# FPGA_Connector_1.net
KiCad netlist of a schematic drawn in Altium Designer
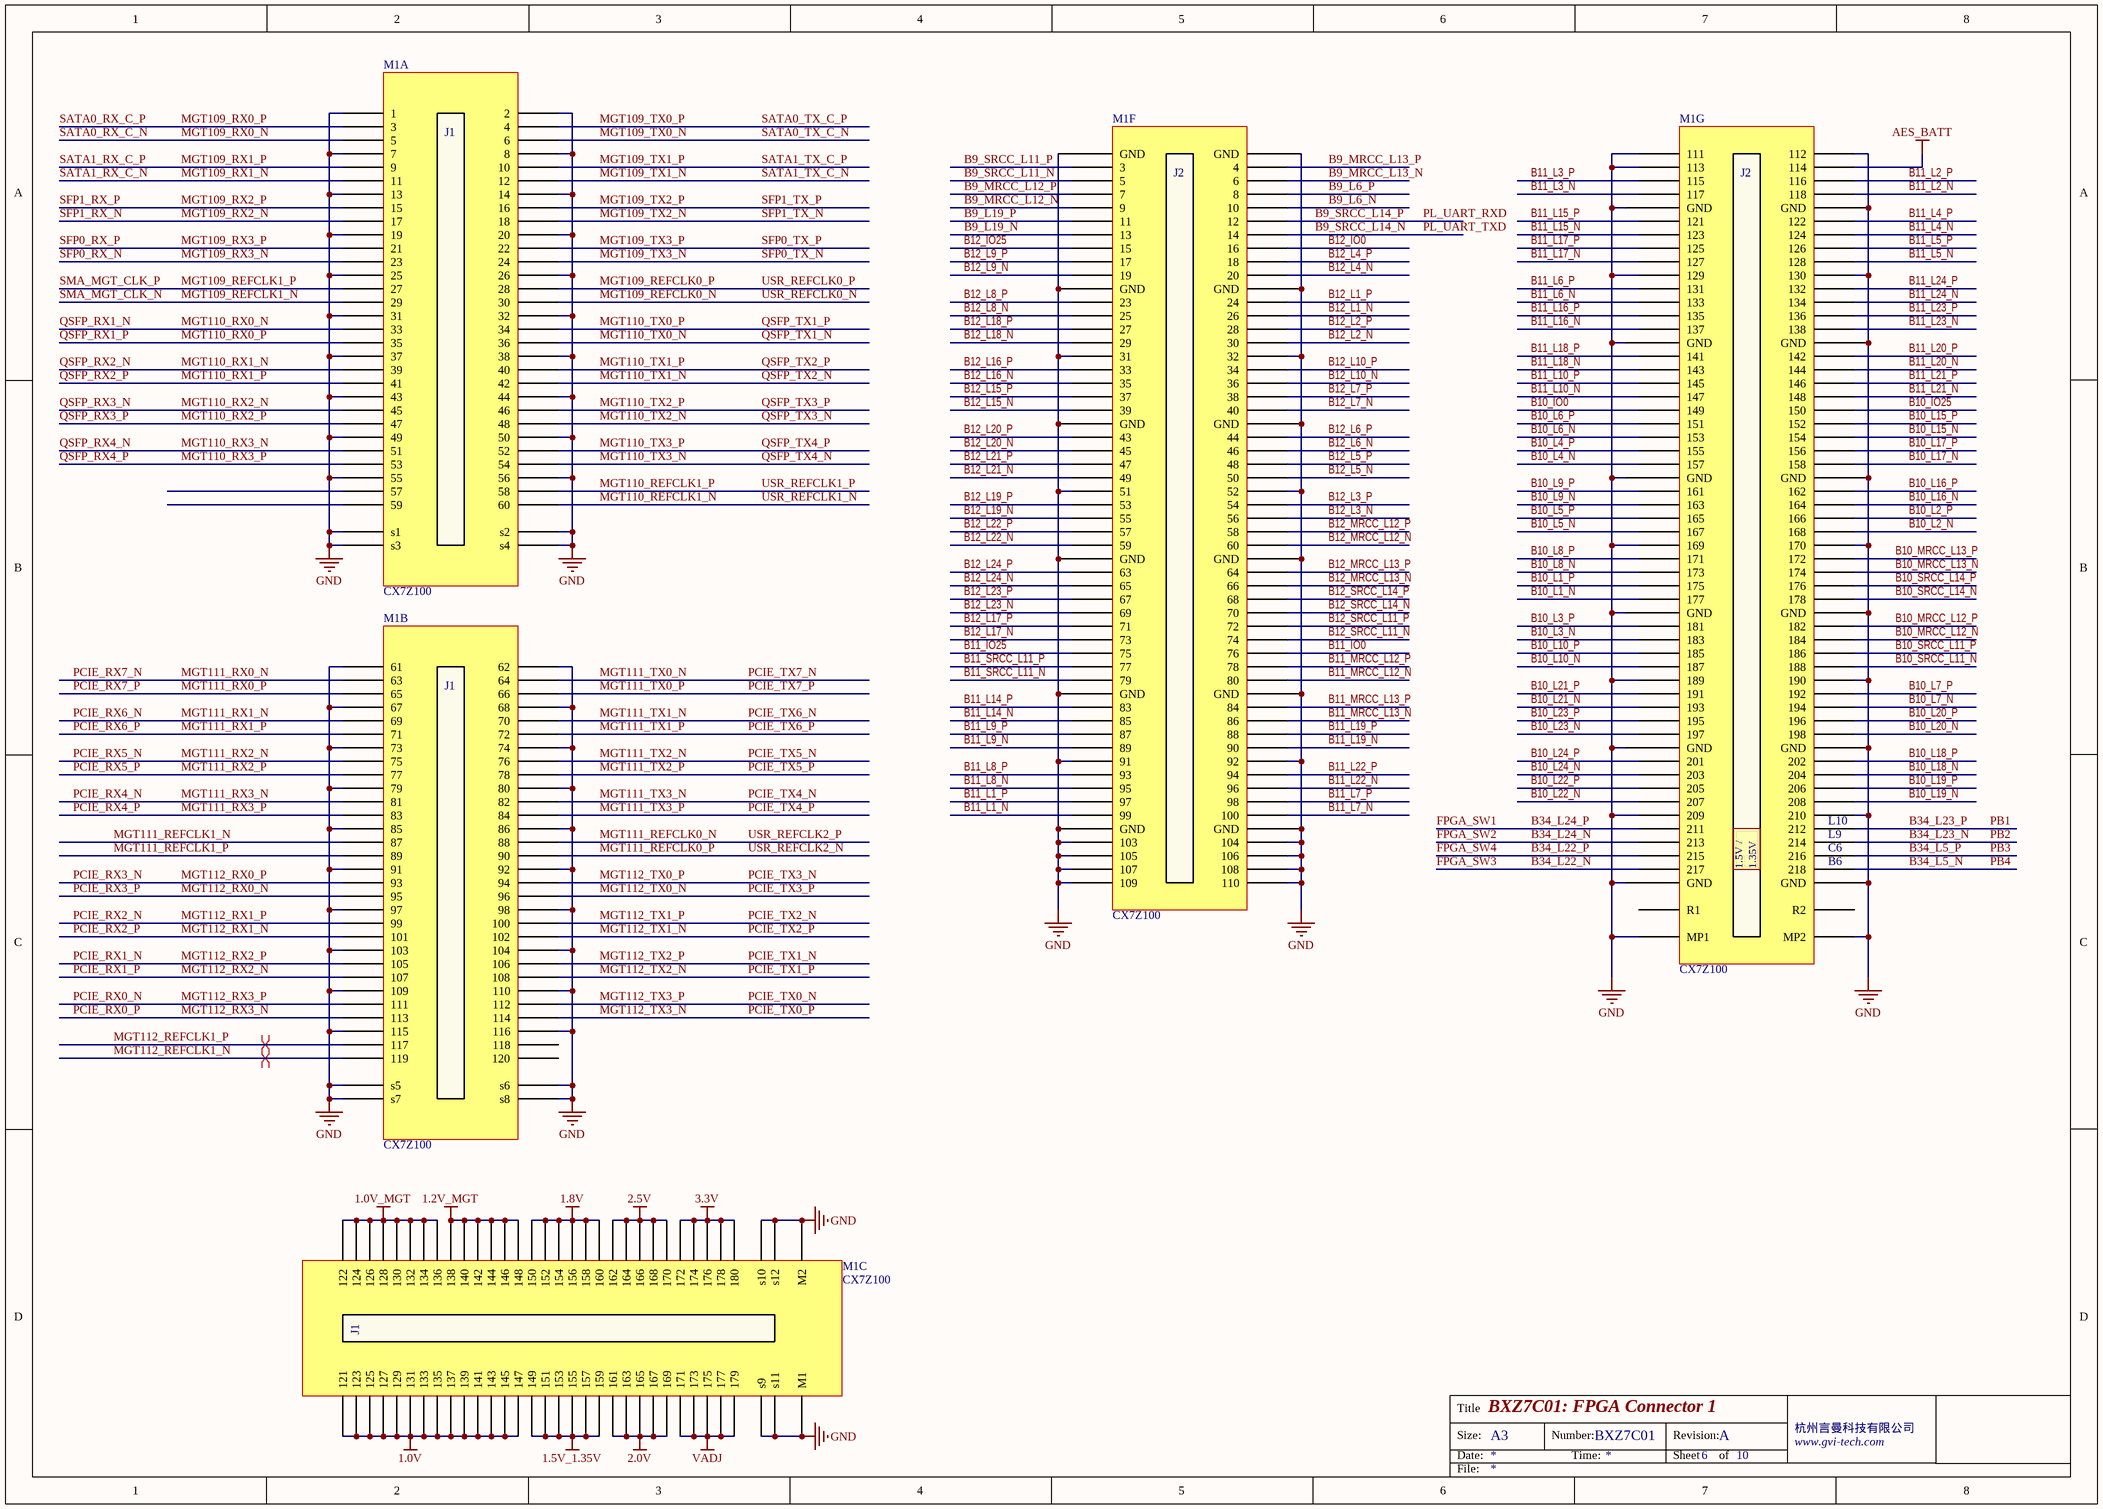
[diagram p0: FPGA_Connector_1.SchDoc]

(export (version "E")
  (design (tool "Eeschema 10.0.6"))
  (components
    (comp (ref "M1")
      (value "CX7Z100")
      (footprint "GVI_Z7_MiniModule_Socket")
      (libsource (lib "GVI_Z7_Carrier") (part "CX7Z100"))
    )
  )
  (nets
    (net (code "1") (name "/B9_L6_N") (class "Default")
      (node (ref "M1") (pin "B10") (pinfunction "10_B10") (pintype "passive"))
    )
    (net (code "2") (name "/B9_L6_P") (class "Default")
      (node (ref "M1") (pin "B8") (pinfunction "8_B8") (pintype "passive"))
    )
    (net (code "3") (name "/B9_L19_N") (class "Default")
      (node (ref "M1") (pin "B13") (pinfunction "13_B13") (pintype "passive"))
    )
    (net (code "4") (name "/B9_L19_P") (class "Default")
      (node (ref "M1") (pin "B11") (pinfunction "11_B11") (pintype "passive"))
    )
    (net (code "5") (name "/B9_MRCC_L12_N") (class "Default")
      (node (ref "M1") (pin "B9") (pinfunction "9_B9") (pintype "passive"))
    )
    (net (code "6") (name "/B9_MRCC_L12_P") (class "Default")
      (node (ref "M1") (pin "B7") (pinfunction "7_B7") (pintype "passive"))
    )
    (net (code "7") (name "/B9_MRCC_L13_N") (class "Default")
      (node (ref "M1") (pin "B6") (pinfunction "6_B6") (pintype "passive"))
    )
    (net (code "8") (name "/B9_MRCC_L13_P") (class "Default")
      (node (ref "M1") (pin "B4") (pinfunction "4_B4") (pintype "passive"))
    )
    (net (code "9") (name "/B9_SRCC_L11_N") (class "Default")
      (node (ref "M1") (pin "B5") (pinfunction "5_B5") (pintype "passive"))
    )
    (net (code "10") (name "/B9_SRCC_L11_P") (class "Default")
      (node (ref "M1") (pin "B3") (pinfunction "3_B3") (pintype "passive"))
    )
    (net (code "11") (name "/B9_SRCC_L14_N") (class "Default")
      (node (ref "M1") (pin "B14") (pinfunction "14_B14") (pintype "passive"))
    )
    (net (code "12") (name "/B9_SRCC_L14_P") (class "Default")
      (node (ref "M1") (pin "B12") (pinfunction "12_B12") (pintype "passive"))
    )
    (net (code "13") (name "/B10_IO0") (class "Default")
      (node (ref "M1") (pin "B149") (pinfunction "149_B149") (pintype "passive"))
    )
    (net (code "14") (name "/B10_IO25") (class "Default")
      (node (ref "M1") (pin "B150") (pinfunction "150_B150") (pintype "passive"))
    )
    (net (code "15") (name "/B10_L1_N") (class "Default")
      (node (ref "M1") (pin "B177") (pinfunction "177_B177") (pintype "passive"))
    )
    (net (code "16") (name "/B10_L1_P") (class "Default")
      (node (ref "M1") (pin "B175") (pinfunction "175_B175") (pintype "passive"))
    )
    (net (code "17") (name "/B10_L2_N") (class "Default")
      (node (ref "M1") (pin "B168") (pinfunction "168_B168") (pintype "passive"))
    )
    (net (code "18") (name "/B10_L2_P") (class "Default")
      (node (ref "M1") (pin "B166") (pinfunction "166_B166") (pintype "passive"))
    )
    (net (code "19") (name "/B10_L3_N") (class "Default")
      (node (ref "M1") (pin "B183") (pinfunction "183_B183") (pintype "passive"))
    )
    (net (code "20") (name "/B10_L3_P") (class "Default")
      (node (ref "M1") (pin "B181") (pinfunction "181_B181") (pintype "passive"))
    )
    (net (code "21") (name "/B10_L4_N") (class "Default")
      (node (ref "M1") (pin "B157") (pinfunction "157_B157") (pintype "passive"))
    )
    (net (code "22") (name "/B10_L4_P") (class "Default")
      (node (ref "M1") (pin "B155") (pinfunction "155_B155") (pintype "passive"))
    )
    (net (code "23") (name "/B10_L5_N") (class "Default")
      (node (ref "M1") (pin "B167") (pinfunction "167_B167") (pintype "passive"))
    )
    (net (code "24") (name "/B10_L5_P") (class "Default")
      (node (ref "M1") (pin "B165") (pinfunction "165_B165") (pintype "passive"))
    )
    (net (code "25") (name "/B10_L6_N") (class "Default")
      (node (ref "M1") (pin "B153") (pinfunction "153_B153") (pintype "passive"))
    )
    (net (code "26") (name "/B10_L6_P") (class "Default")
      (node (ref "M1") (pin "B151") (pinfunction "151_B151") (pintype "passive"))
    )
    (net (code "27") (name "/B10_L7_N") (class "Default")
      (node (ref "M1") (pin "B194") (pinfunction "194_B194") (pintype "passive"))
    )
    (net (code "28") (name "/B10_L7_P") (class "Default")
      (node (ref "M1") (pin "B192") (pinfunction "192_B192") (pintype "passive"))
    )
    (net (code "29") (name "/B10_L8_N") (class "Default")
      (node (ref "M1") (pin "B173") (pinfunction "173_B173") (pintype "passive"))
    )
    (net (code "30") (name "/B10_L8_P") (class "Default")
      (node (ref "M1") (pin "B171") (pinfunction "171_B171") (pintype "passive"))
    )
    (net (code "31") (name "/B10_L9_N") (class "Default")
      (node (ref "M1") (pin "B163") (pinfunction "163_B163") (pintype "passive"))
    )
    (net (code "32") (name "/B10_L9_P") (class "Default")
      (node (ref "M1") (pin "B161") (pinfunction "161_B161") (pintype "passive"))
    )
    (net (code "33") (name "/B10_L10_N") (class "Default")
      (node (ref "M1") (pin "B187") (pinfunction "187_B187") (pintype "passive"))
    )
    (net (code "34") (name "/B10_L10_P") (class "Default")
      (node (ref "M1") (pin "B185") (pinfunction "185_B185") (pintype "passive"))
    )
    (net (code "35") (name "/B10_L15_N") (class "Default")
      (node (ref "M1") (pin "B154") (pinfunction "154_B154") (pintype "passive"))
    )
    (net (code "36") (name "/B10_L15_P") (class "Default")
      (node (ref "M1") (pin "B152") (pinfunction "152_B152") (pintype "passive"))
    )
    (net (code "37") (name "/B10_L16_N") (class "Default")
      (node (ref "M1") (pin "B164") (pinfunction "164_B164") (pintype "passive"))
    )
    (net (code "38") (name "/B10_L16_P") (class "Default")
      (node (ref "M1") (pin "B162") (pinfunction "162_B162") (pintype "passive"))
    )
    (net (code "39") (name "/B10_L17_N") (class "Default")
      (node (ref "M1") (pin "B158") (pinfunction "158_B158") (pintype "passive"))
    )
    (net (code "40") (name "/B10_L17_P") (class "Default")
      (node (ref "M1") (pin "B156") (pinfunction "156_B156") (pintype "passive"))
    )
    (net (code "41") (name "/B10_L18_N") (class "Default")
      (node (ref "M1") (pin "B204") (pinfunction "204_B204") (pintype "passive"))
    )
    (net (code "42") (name "/B10_L18_P") (class "Default")
      (node (ref "M1") (pin "B202") (pinfunction "202_B202") (pintype "passive"))
    )
    (net (code "43") (name "/B10_L19_N") (class "Default")
      (node (ref "M1") (pin "B208") (pinfunction "208_B208") (pintype "passive"))
    )
    (net (code "44") (name "/B10_L19_P") (class "Default")
      (node (ref "M1") (pin "B206") (pinfunction "206_B206") (pintype "passive"))
    )
    (net (code "45") (name "/B10_L20_N") (class "Default")
      (node (ref "M1") (pin "B198") (pinfunction "198_B198") (pintype "passive"))
    )
    (net (code "46") (name "/B10_L20_P") (class "Default")
      (node (ref "M1") (pin "B196") (pinfunction "196_B196") (pintype "passive"))
    )
    (net (code "47") (name "/B10_L21_N") (class "Default")
      (node (ref "M1") (pin "B193") (pinfunction "193_B193") (pintype "passive"))
    )
    (net (code "48") (name "/B10_L21_P") (class "Default")
      (node (ref "M1") (pin "B191") (pinfunction "191_B191") (pintype "passive"))
    )
    (net (code "49") (name "/B10_L22_N") (class "Default")
      (node (ref "M1") (pin "B207") (pinfunction "207_B207") (pintype "passive"))
    )
    (net (code "50") (name "/B10_L22_P") (class "Default")
      (node (ref "M1") (pin "B205") (pinfunction "205_B205") (pintype "passive"))
    )
    (net (code "51") (name "/B10_L23_N") (class "Default")
      (node (ref "M1") (pin "B197") (pinfunction "197_B197") (pintype "passive"))
    )
    (net (code "52") (name "/B10_L23_P") (class "Default")
      (node (ref "M1") (pin "B195") (pinfunction "195_B195") (pintype "passive"))
    )
    (net (code "53") (name "/B10_L24_N") (class "Default")
      (node (ref "M1") (pin "B203") (pinfunction "203_B203") (pintype "passive"))
    )
    (net (code "54") (name "/B10_L24_P") (class "Default")
      (node (ref "M1") (pin "B201") (pinfunction "201_B201") (pintype "passive"))
    )
    (net (code "55") (name "/B10_MRCC_L12_N") (class "Default")
      (node (ref "M1") (pin "B184") (pinfunction "184_B184") (pintype "passive"))
    )
    (net (code "56") (name "/B10_MRCC_L12_P") (class "Default")
      (node (ref "M1") (pin "B182") (pinfunction "182_B182") (pintype "passive"))
    )
    (net (code "57") (name "/B10_MRCC_L13_N") (class "Default")
      (node (ref "M1") (pin "B174") (pinfunction "174_B174") (pintype "passive"))
    )
    (net (code "58") (name "/B10_MRCC_L13_P") (class "Default")
      (node (ref "M1") (pin "B172") (pinfunction "172_B172") (pintype "passive"))
    )
    (net (code "59") (name "/B10_SRCC_L11_N") (class "Default")
      (node (ref "M1") (pin "B188") (pinfunction "188_B188") (pintype "passive"))
    )
    (net (code "60") (name "/B10_SRCC_L11_P") (class "Default")
      (node (ref "M1") (pin "B186") (pinfunction "186_B186") (pintype "passive"))
    )
    (net (code "61") (name "/B10_SRCC_L14_N") (class "Default")
      (node (ref "M1") (pin "B178") (pinfunction "178_B178") (pintype "passive"))
    )
    (net (code "62") (name "/B10_SRCC_L14_P") (class "Default")
      (node (ref "M1") (pin "B176") (pinfunction "176_B176") (pintype "passive"))
    )
    (net (code "63") (name "/B11_IO0") (class "Default")
      (node (ref "M1") (pin "B76") (pinfunction "76_B76") (pintype "passive"))
    )
    (net (code "64") (name "/B11_IO25") (class "Default")
      (node (ref "M1") (pin "B75") (pinfunction "75_B75") (pintype "passive"))
    )
    (net (code "65") (name "/B11_L1_N") (class "Default")
      (node (ref "M1") (pin "B99") (pinfunction "99_B99") (pintype "passive"))
    )
    (net (code "66") (name "/B11_L1_P") (class "Default")
      (node (ref "M1") (pin "B97") (pinfunction "97_B97") (pintype "passive"))
    )
    (net (code "67") (name "/B11_L2_N") (class "Default")
      (node (ref "M1") (pin "B118") (pinfunction "118_B118") (pintype "passive"))
    )
    (net (code "68") (name "/B11_L2_P") (class "Default")
      (node (ref "M1") (pin "B116") (pinfunction "116_B116") (pintype "passive"))
    )
    (net (code "69") (name "/B11_L3_N") (class "Default")
      (node (ref "M1") (pin "B117") (pinfunction "117_B117") (pintype "passive"))
    )
    (net (code "70") (name "/B11_L3_P") (class "Default")
      (node (ref "M1") (pin "B115") (pinfunction "115_B115") (pintype "passive"))
    )
    (net (code "71") (name "/B11_L4_N") (class "Default")
      (node (ref "M1") (pin "B124") (pinfunction "124_B124") (pintype "passive"))
    )
    (net (code "72") (name "/B11_L4_P") (class "Default")
      (node (ref "M1") (pin "B122") (pinfunction "122_B122") (pintype "passive"))
    )
    (net (code "73") (name "/B11_L5_N") (class "Default")
      (node (ref "M1") (pin "B128") (pinfunction "128_B128") (pintype "passive"))
    )
    (net (code "74") (name "/B11_L5_P") (class "Default")
      (node (ref "M1") (pin "B126") (pinfunction "126_B126") (pintype "passive"))
    )
    (net (code "75") (name "/B11_L6_N") (class "Default")
      (node (ref "M1") (pin "B133") (pinfunction "133_B133") (pintype "passive"))
    )
    (net (code "76") (name "/B11_L6_P") (class "Default")
      (node (ref "M1") (pin "B131") (pinfunction "131_B131") (pintype "passive"))
    )
    (net (code "77") (name "/B11_L7_N") (class "Default")
      (node (ref "M1") (pin "B100") (pinfunction "100_B100") (pintype "passive"))
    )
    (net (code "78") (name "/B11_L7_P") (class "Default")
      (node (ref "M1") (pin "B98") (pinfunction "98_B98") (pintype "passive"))
    )
    (net (code "79") (name "/B11_L8_N") (class "Default")
      (node (ref "M1") (pin "B95") (pinfunction "95_B95") (pintype "passive"))
    )
    (net (code "80") (name "/B11_L8_P") (class "Default")
      (node (ref "M1") (pin "B93") (pinfunction "93_B93") (pintype "passive"))
    )
    (net (code "81") (name "/B11_L9_N") (class "Default")
      (node (ref "M1") (pin "B89") (pinfunction "89_B89") (pintype "passive"))
    )
    (net (code "82") (name "/B11_L9_P") (class "Default")
      (node (ref "M1") (pin "B87") (pinfunction "87_B87") (pintype "passive"))
    )
    (net (code "83") (name "/B11_L10_N") (class "Default")
      (node (ref "M1") (pin "B147") (pinfunction "147_B147") (pintype "passive"))
    )
    (net (code "84") (name "/B11_L10_P") (class "Default")
      (node (ref "M1") (pin "B145") (pinfunction "145_B145") (pintype "passive"))
    )
    (net (code "85") (name "/B11_L14_N") (class "Default")
      (node (ref "M1") (pin "B85") (pinfunction "85_B85") (pintype "passive"))
    )
    (net (code "86") (name "/B11_L14_P") (class "Default")
      (node (ref "M1") (pin "B83") (pinfunction "83_B83") (pintype "passive"))
    )
    (net (code "87") (name "/B11_L15_N") (class "Default")
      (node (ref "M1") (pin "B123") (pinfunction "123_B123") (pintype "passive"))
    )
    (net (code "88") (name "/B11_L15_P") (class "Default")
      (node (ref "M1") (pin "B121") (pinfunction "121_B121") (pintype "passive"))
    )
    (net (code "89") (name "/B11_L16_N") (class "Default")
      (node (ref "M1") (pin "B137") (pinfunction "137_B137") (pintype "passive"))
    )
    (net (code "90") (name "/B11_L16_P") (class "Default")
      (node (ref "M1") (pin "B135") (pinfunction "135_B135") (pintype "passive"))
    )
    (net (code "91") (name "/B11_L17_N") (class "Default")
      (node (ref "M1") (pin "B127") (pinfunction "127_B127") (pintype "passive"))
    )
    (net (code "92") (name "/B11_L17_P") (class "Default")
      (node (ref "M1") (pin "B125") (pinfunction "125_B125") (pintype "passive"))
    )
    (net (code "93") (name "/B11_L18_N") (class "Default")
      (node (ref "M1") (pin "B143") (pinfunction "143_B143") (pintype "passive"))
    )
    (net (code "94") (name "/B11_L18_P") (class "Default")
      (node (ref "M1") (pin "B141") (pinfunction "141_B141") (pintype "passive"))
    )
    (net (code "95") (name "/B11_L19_N") (class "Default")
      (node (ref "M1") (pin "B90") (pinfunction "90_B90") (pintype "passive"))
    )
    (net (code "96") (name "/B11_L19_P") (class "Default")
      (node (ref "M1") (pin "B88") (pinfunction "88_B88") (pintype "passive"))
    )
    (net (code "97") (name "/B11_L20_N") (class "Default")
      (node (ref "M1") (pin "B144") (pinfunction "144_B144") (pintype "passive"))
    )
    (net (code "98") (name "/B11_L20_P") (class "Default")
      (node (ref "M1") (pin "B142") (pinfunction "142_B142") (pintype "passive"))
    )
    (net (code "99") (name "/B11_L21_N") (class "Default")
      (node (ref "M1") (pin "B148") (pinfunction "148_B148") (pintype "passive"))
    )
    (net (code "100") (name "/B11_L21_P") (class "Default")
      (node (ref "M1") (pin "B146") (pinfunction "146_B146") (pintype "passive"))
    )
    (net (code "101") (name "/B11_L22_N") (class "Default")
      (node (ref "M1") (pin "B96") (pinfunction "96_B96") (pintype "passive"))
    )
    (net (code "102") (name "/B11_L22_P") (class "Default")
      (node (ref "M1") (pin "B94") (pinfunction "94_B94") (pintype "passive"))
    )
    (net (code "103") (name "/B11_L23_N") (class "Default")
      (node (ref "M1") (pin "B138") (pinfunction "138_B138") (pintype "passive"))
    )
    (net (code "104") (name "/B11_L23_P") (class "Default")
      (node (ref "M1") (pin "B136") (pinfunction "136_B136") (pintype "passive"))
    )
    (net (code "105") (name "/B11_L24_N") (class "Default")
      (node (ref "M1") (pin "B134") (pinfunction "134_B134") (pintype "passive"))
    )
    (net (code "106") (name "/B11_L24_P") (class "Default")
      (node (ref "M1") (pin "B132") (pinfunction "132_B132") (pintype "passive"))
    )
    (net (code "107") (name "/B11_MRCC_L12_N") (class "Default")
      (node (ref "M1") (pin "B80") (pinfunction "80_B80") (pintype "passive"))
    )
    (net (code "108") (name "/B11_MRCC_L12_P") (class "Default")
      (node (ref "M1") (pin "B78") (pinfunction "78_B78") (pintype "passive"))
    )
    (net (code "109") (name "/B11_MRCC_L13_N") (class "Default")
      (node (ref "M1") (pin "B86") (pinfunction "86_B86") (pintype "passive"))
    )
    (net (code "110") (name "/B11_MRCC_L13_P") (class "Default")
      (node (ref "M1") (pin "B84") (pinfunction "84_B84") (pintype "passive"))
    )
    (net (code "111") (name "/B11_SRCC_L11_N") (class "Default")
      (node (ref "M1") (pin "B79") (pinfunction "79_B79") (pintype "passive"))
    )
    (net (code "112") (name "/B11_SRCC_L11_P") (class "Default")
      (node (ref "M1") (pin "B77") (pinfunction "77_B77") (pintype "passive"))
    )
    (net (code "113") (name "/B12_IO0") (class "Default")
      (node (ref "M1") (pin "B16") (pinfunction "16_B16") (pintype "passive"))
    )
    (net (code "114") (name "/B12_IO25") (class "Default")
      (node (ref "M1") (pin "B15") (pinfunction "15_B15") (pintype "passive"))
    )
    (net (code "115") (name "/B12_L1_N") (class "Default")
      (node (ref "M1") (pin "B26") (pinfunction "26_B26") (pintype "passive"))
    )
    (net (code "116") (name "/B12_L1_P") (class "Default")
      (node (ref "M1") (pin "B24") (pinfunction "24_B24") (pintype "passive"))
    )
    (net (code "117") (name "/B12_L2_N") (class "Default")
      (node (ref "M1") (pin "B30") (pinfunction "30_B30") (pintype "passive"))
    )
    (net (code "118") (name "/B12_L2_P") (class "Default")
      (node (ref "M1") (pin "B28") (pinfunction "28_B28") (pintype "passive"))
    )
    (net (code "119") (name "/B12_L3_N") (class "Default")
      (node (ref "M1") (pin "B56") (pinfunction "56_B56") (pintype "passive"))
    )
    (net (code "120") (name "/B12_L3_P") (class "Default")
      (node (ref "M1") (pin "B54") (pinfunction "54_B54") (pintype "passive"))
    )
    (net (code "121") (name "/B12_L4_N") (class "Default")
      (node (ref "M1") (pin "B20") (pinfunction "20_B20") (pintype "passive"))
    )
    (net (code "122") (name "/B12_L4_P") (class "Default")
      (node (ref "M1") (pin "B18") (pinfunction "18_B18") (pintype "passive"))
    )
    (net (code "123") (name "/B12_L5_N") (class "Default")
      (node (ref "M1") (pin "B50") (pinfunction "50_B50") (pintype "passive"))
    )
    (net (code "124") (name "/B12_L5_P") (class "Default")
      (node (ref "M1") (pin "B48") (pinfunction "48_B48") (pintype "passive"))
    )
    (net (code "125") (name "/B12_L6_N") (class "Default")
      (node (ref "M1") (pin "B46") (pinfunction "46_B46") (pintype "passive"))
    )
    (net (code "126") (name "/B12_L6_P") (class "Default")
      (node (ref "M1") (pin "B44") (pinfunction "44_B44") (pintype "passive"))
    )
    (net (code "127") (name "/B12_L7_N") (class "Default")
      (node (ref "M1") (pin "B40") (pinfunction "40_B40") (pintype "passive"))
    )
    (net (code "128") (name "/B12_L7_P") (class "Default")
      (node (ref "M1") (pin "B38") (pinfunction "38_B38") (pintype "passive"))
    )
    (net (code "129") (name "/B12_L8_N") (class "Default")
      (node (ref "M1") (pin "B25") (pinfunction "25_B25") (pintype "passive"))
    )
    (net (code "130") (name "/B12_L8_P") (class "Default")
      (node (ref "M1") (pin "B23") (pinfunction "23_B23") (pintype "passive"))
    )
    (net (code "131") (name "/B12_L9_N") (class "Default")
      (node (ref "M1") (pin "B19") (pinfunction "19_B19") (pintype "passive"))
    )
    (net (code "132") (name "/B12_L9_P") (class "Default")
      (node (ref "M1") (pin "B17") (pinfunction "17_B17") (pintype "passive"))
    )
    (net (code "133") (name "/B12_L10_N") (class "Default")
      (node (ref "M1") (pin "B36") (pinfunction "36_B36") (pintype "passive"))
    )
    (net (code "134") (name "/B12_L10_P") (class "Default")
      (node (ref "M1") (pin "B34") (pinfunction "34_B34") (pintype "passive"))
    )
    (net (code "135") (name "/B12_L15_N") (class "Default")
      (node (ref "M1") (pin "B39") (pinfunction "39_B39") (pintype "passive"))
    )
    (net (code "136") (name "/B12_L15_P") (class "Default")
      (node (ref "M1") (pin "B37") (pinfunction "37_B37") (pintype "passive"))
    )
    (net (code "137") (name "/B12_L16_N") (class "Default")
      (node (ref "M1") (pin "B35") (pinfunction "35_B35") (pintype "passive"))
    )
    (net (code "138") (name "/B12_L16_P") (class "Default")
      (node (ref "M1") (pin "B33") (pinfunction "33_B33") (pintype "passive"))
    )
    (net (code "139") (name "/B12_L17_N") (class "Default")
      (node (ref "M1") (pin "B73") (pinfunction "73_B73") (pintype "passive"))
    )
    (net (code "140") (name "/B12_L17_P") (class "Default")
      (node (ref "M1") (pin "B71") (pinfunction "71_B71") (pintype "passive"))
    )
    (net (code "141") (name "/B12_L18_N") (class "Default")
      (node (ref "M1") (pin "B29") (pinfunction "29_B29") (pintype "passive"))
    )
    (net (code "142") (name "/B12_L18_P") (class "Default")
      (node (ref "M1") (pin "B27") (pinfunction "27_B27") (pintype "passive"))
    )
    (net (code "143") (name "/B12_L19_N") (class "Default")
      (node (ref "M1") (pin "B55") (pinfunction "55_B55") (pintype "passive"))
    )
    (net (code "144") (name "/B12_L19_P") (class "Default")
      (node (ref "M1") (pin "B53") (pinfunction "53_B53") (pintype "passive"))
    )
    (net (code "145") (name "/B12_L20_N") (class "Default")
      (node (ref "M1") (pin "B45") (pinfunction "45_B45") (pintype "passive"))
    )
    (net (code "146") (name "/B12_L20_P") (class "Default")
      (node (ref "M1") (pin "B43") (pinfunction "43_B43") (pintype "passive"))
    )
    (net (code "147") (name "/B12_L21_N") (class "Default")
      (node (ref "M1") (pin "B49") (pinfunction "49_B49") (pintype "passive"))
    )
    (net (code "148") (name "/B12_L21_P") (class "Default")
      (node (ref "M1") (pin "B47") (pinfunction "47_B47") (pintype "passive"))
    )
    (net (code "149") (name "/B12_L22_N") (class "Default")
      (node (ref "M1") (pin "B59") (pinfunction "59_B59") (pintype "passive"))
    )
    (net (code "150") (name "/B12_L22_P") (class "Default")
      (node (ref "M1") (pin "B57") (pinfunction "57_B57") (pintype "passive"))
    )
    (net (code "151") (name "/B12_L23_N") (class "Default")
      (node (ref "M1") (pin "B69") (pinfunction "69_B69") (pintype "passive"))
    )
    (net (code "152") (name "/B12_L23_P") (class "Default")
      (node (ref "M1") (pin "B67") (pinfunction "67_B67") (pintype "passive"))
    )
    (net (code "153") (name "/B12_L24_N") (class "Default")
      (node (ref "M1") (pin "B65") (pinfunction "65_B65") (pintype "passive"))
    )
    (net (code "154") (name "/B12_L24_P") (class "Default")
      (node (ref "M1") (pin "B63") (pinfunction "63_B63") (pintype "passive"))
    )
    (net (code "155") (name "/B12_MRCC_L12_N") (class "Default")
      (node (ref "M1") (pin "B60") (pinfunction "60_B60") (pintype "passive"))
    )
    (net (code "156") (name "/B12_MRCC_L12_P") (class "Default")
      (node (ref "M1") (pin "B58") (pinfunction "58_B58") (pintype "passive"))
    )
    (net (code "157") (name "/B12_MRCC_L13_N") (class "Default")
      (node (ref "M1") (pin "B66") (pinfunction "66_B66") (pintype "passive"))
    )
    (net (code "158") (name "/B12_MRCC_L13_P") (class "Default")
      (node (ref "M1") (pin "B64") (pinfunction "64_B64") (pintype "passive"))
    )
    (net (code "159") (name "/B12_SRCC_L11_N") (class "Default")
      (node (ref "M1") (pin "B74") (pinfunction "74_B74") (pintype "passive"))
    )
    (net (code "160") (name "/B12_SRCC_L11_P") (class "Default")
      (node (ref "M1") (pin "B72") (pinfunction "72_B72") (pintype "passive"))
    )
    (net (code "161") (name "/B12_SRCC_L14_N") (class "Default")
      (node (ref "M1") (pin "B70") (pinfunction "70_B70") (pintype "passive"))
    )
    (net (code "162") (name "/B12_SRCC_L14_P") (class "Default")
      (node (ref "M1") (pin "B68") (pinfunction "68_B68") (pintype "passive"))
    )
    (net (code "163") (name "/B34_L5_N") (class "Default")
      (node (ref "M1") (pin "B218") (pinfunction "218_B218") (pintype "passive"))
    )
    (net (code "164") (name "/B34_L5_P") (class "Default")
      (node (ref "M1") (pin "B216") (pinfunction "216_B216") (pintype "passive"))
    )
    (net (code "165") (name "/B34_L22_N") (class "Default")
      (node (ref "M1") (pin "B217") (pinfunction "217_B217") (pintype "passive"))
    )
    (net (code "166") (name "/B34_L22_P") (class "Default")
      (node (ref "M1") (pin "B215") (pinfunction "215_B215") (pintype "passive"))
    )
    (net (code "167") (name "/B34_L23_N") (class "Default")
      (node (ref "M1") (pin "B214") (pinfunction "214_B214") (pintype "passive"))
    )
    (net (code "168") (name "/B34_L23_P") (class "Default")
      (node (ref "M1") (pin "B212") (pinfunction "212_B212") (pintype "passive"))
    )
    (net (code "169") (name "/B34_L24_N") (class "Default")
      (node (ref "M1") (pin "B213") (pinfunction "213_B213") (pintype "passive"))
    )
    (net (code "170") (name "/B34_L24_P") (class "Default")
      (node (ref "M1") (pin "B211") (pinfunction "211_B211") (pintype "passive"))
    )
    (net (code "171") (name "/MGT109_REFCLK0_N") (class "Default")
      (node (ref "M1") (pin "30") (pinfunction "30_30") (pintype "passive"))
    )
    (net (code "172") (name "/MGT109_REFCLK0_P") (class "Default")
      (node (ref "M1") (pin "28") (pinfunction "28_28") (pintype "passive"))
    )
    (net (code "173") (name "/MGT109_REFCLK1_N") (class "Default")
      (node (ref "M1") (pin "29") (pinfunction "29_29") (pintype "passive"))
    )
    (net (code "174") (name "/MGT109_REFCLK1_P") (class "Default")
      (node (ref "M1") (pin "27") (pinfunction "27_27") (pintype "passive"))
    )
    (net (code "175") (name "/MGT109_RX0_N") (class "Default")
      (node (ref "M1") (pin "5") (pinfunction "5_5") (pintype "passive"))
    )
    (net (code "176") (name "/MGT109_RX0_P") (class "Default")
      (node (ref "M1") (pin "3") (pinfunction "3_3") (pintype "passive"))
    )
    (net (code "177") (name "/MGT109_RX1_N") (class "Default")
      (node (ref "M1") (pin "11") (pinfunction "11_11") (pintype "passive"))
    )
    (net (code "178") (name "/MGT109_RX1_P") (class "Default")
      (node (ref "M1") (pin "9") (pinfunction "9_9") (pintype "passive"))
    )
    (net (code "179") (name "/MGT109_RX2_N") (class "Default")
      (node (ref "M1") (pin "17") (pinfunction "17_17") (pintype "passive"))
    )
    (net (code "180") (name "/MGT109_RX2_P") (class "Default")
      (node (ref "M1") (pin "15") (pinfunction "15_15") (pintype "passive"))
    )
    (net (code "181") (name "/MGT109_RX3_N") (class "Default")
      (node (ref "M1") (pin "23") (pinfunction "23_23") (pintype "passive"))
    )
    (net (code "182") (name "/MGT109_RX3_P") (class "Default")
      (node (ref "M1") (pin "21") (pinfunction "21_21") (pintype "passive"))
    )
    (net (code "183") (name "/MGT109_TX0_N") (class "Default")
      (node (ref "M1") (pin "6") (pinfunction "6_6") (pintype "passive"))
    )
    (net (code "184") (name "/MGT109_TX0_P") (class "Default")
      (node (ref "M1") (pin "4") (pinfunction "4_4") (pintype "passive"))
    )
    (net (code "185") (name "/MGT109_TX1_N") (class "Default")
      (node (ref "M1") (pin "12") (pinfunction "12_12") (pintype "passive"))
    )
    (net (code "186") (name "/MGT109_TX1_P") (class "Default")
      (node (ref "M1") (pin "10") (pinfunction "10_10") (pintype "passive"))
    )
    (net (code "187") (name "/MGT109_TX2_N") (class "Default")
      (node (ref "M1") (pin "18") (pinfunction "18_18") (pintype "passive"))
    )
    (net (code "188") (name "/MGT109_TX2_P") (class "Default")
      (node (ref "M1") (pin "16") (pinfunction "16_16") (pintype "passive"))
    )
    (net (code "189") (name "/MGT109_TX3_N") (class "Default")
      (node (ref "M1") (pin "24") (pinfunction "24_24") (pintype "passive"))
    )
    (net (code "190") (name "/MGT109_TX3_P") (class "Default")
      (node (ref "M1") (pin "22") (pinfunction "22_22") (pintype "passive"))
    )
    (net (code "191") (name "/MGT110_REFCLK1_N") (class "Default")
      (node (ref "M1") (pin "60") (pinfunction "60_60") (pintype "passive"))
    )
    (net (code "192") (name "/MGT110_REFCLK1_P") (class "Default")
      (node (ref "M1") (pin "58") (pinfunction "58_58") (pintype "passive"))
    )
    (net (code "193") (name "/MGT110_RX0_N") (class "Default")
      (node (ref "M1") (pin "33") (pinfunction "33_33") (pintype "passive"))
    )
    (net (code "194") (name "/MGT110_RX0_P") (class "Default")
      (node (ref "M1") (pin "35") (pinfunction "35_35") (pintype "passive"))
    )
    (net (code "195") (name "/MGT110_RX1_N") (class "Default")
      (node (ref "M1") (pin "39") (pinfunction "39_39") (pintype "passive"))
    )
    (net (code "196") (name "/MGT110_RX1_P") (class "Default")
      (node (ref "M1") (pin "41") (pinfunction "41_41") (pintype "passive"))
    )
    (net (code "197") (name "/MGT110_RX2_N") (class "Default")
      (node (ref "M1") (pin "45") (pinfunction "45_45") (pintype "passive"))
    )
    (net (code "198") (name "/MGT110_RX2_P") (class "Default")
      (node (ref "M1") (pin "47") (pinfunction "47_47") (pintype "passive"))
    )
    (net (code "199") (name "/MGT110_RX3_N") (class "Default")
      (node (ref "M1") (pin "51") (pinfunction "51_51") (pintype "passive"))
    )
    (net (code "200") (name "/MGT110_RX3_P") (class "Default")
      (node (ref "M1") (pin "53") (pinfunction "53_53") (pintype "passive"))
    )
    (net (code "201") (name "/MGT110_TX0_N") (class "Default")
      (node (ref "M1") (pin "36") (pinfunction "36_36") (pintype "passive"))
    )
    (net (code "202") (name "/MGT110_TX0_P") (class "Default")
      (node (ref "M1") (pin "34") (pinfunction "34_34") (pintype "passive"))
    )
    (net (code "203") (name "/MGT110_TX1_N") (class "Default")
      (node (ref "M1") (pin "42") (pinfunction "42_42") (pintype "passive"))
    )
    (net (code "204") (name "/MGT110_TX1_P") (class "Default")
      (node (ref "M1") (pin "40") (pinfunction "40_40") (pintype "passive"))
    )
    (net (code "205") (name "/MGT110_TX2_N") (class "Default")
      (node (ref "M1") (pin "48") (pinfunction "48_48") (pintype "passive"))
    )
    (net (code "206") (name "/MGT110_TX2_P") (class "Default")
      (node (ref "M1") (pin "46") (pinfunction "46_46") (pintype "passive"))
    )
    (net (code "207") (name "/MGT110_TX3_N") (class "Default")
      (node (ref "M1") (pin "54") (pinfunction "54_54") (pintype "passive"))
    )
    (net (code "208") (name "/MGT110_TX3_P") (class "Default")
      (node (ref "M1") (pin "52") (pinfunction "52_52") (pintype "passive"))
    )
    (net (code "209") (name "/MGT111_REFCLK0_N") (class "Default")
      (node (ref "M1") (pin "88") (pinfunction "88_88") (pintype "passive"))
    )
    (net (code "210") (name "/MGT111_REFCLK0_P") (class "Default")
      (node (ref "M1") (pin "90") (pinfunction "90_90") (pintype "passive"))
    )
    (net (code "211") (name "/MGT111_REFCLK1_N") (class "Default")
      (node (ref "M1") (pin "87") (pinfunction "87_87") (pintype "passive"))
    )
    (net (code "212") (name "/MGT111_REFCLK1_P") (class "Default")
      (node (ref "M1") (pin "89") (pinfunction "89_89") (pintype "passive"))
    )
    (net (code "213") (name "/MGT111_RX0_N") (class "Default")
      (node (ref "M1") (pin "63") (pinfunction "63_63") (pintype "passive"))
    )
    (net (code "214") (name "/MGT111_RX0_P") (class "Default")
      (node (ref "M1") (pin "65") (pinfunction "65_65") (pintype "passive"))
    )
    (net (code "215") (name "/MGT111_RX1_N") (class "Default")
      (node (ref "M1") (pin "69") (pinfunction "69_69") (pintype "passive"))
    )
    (net (code "216") (name "/MGT111_RX1_P") (class "Default")
      (node (ref "M1") (pin "71") (pinfunction "71_71") (pintype "passive"))
    )
    (net (code "217") (name "/MGT111_RX2_N") (class "Default")
      (node (ref "M1") (pin "75") (pinfunction "75_75") (pintype "passive"))
    )
    (net (code "218") (name "/MGT111_RX2_P") (class "Default")
      (node (ref "M1") (pin "77") (pinfunction "77_77") (pintype "passive"))
    )
    (net (code "219") (name "/MGT111_RX3_N") (class "Default")
      (node (ref "M1") (pin "81") (pinfunction "81_81") (pintype "passive"))
    )
    (net (code "220") (name "/MGT111_RX3_P") (class "Default")
      (node (ref "M1") (pin "83") (pinfunction "83_83") (pintype "passive"))
    )
    (net (code "221") (name "/MGT111_TX0_N") (class "Default")
      (node (ref "M1") (pin "64") (pinfunction "64_64") (pintype "passive"))
    )
    (net (code "222") (name "/MGT111_TX0_P") (class "Default")
      (node (ref "M1") (pin "66") (pinfunction "66_66") (pintype "passive"))
    )
    (net (code "223") (name "/MGT111_TX1_N") (class "Default")
      (node (ref "M1") (pin "70") (pinfunction "70_70") (pintype "passive"))
    )
    (net (code "224") (name "/MGT111_TX1_P") (class "Default")
      (node (ref "M1") (pin "72") (pinfunction "72_72") (pintype "passive"))
    )
    (net (code "225") (name "/MGT111_TX2_N") (class "Default")
      (node (ref "M1") (pin "76") (pinfunction "76_76") (pintype "passive"))
    )
    (net (code "226") (name "/MGT111_TX2_P") (class "Default")
      (node (ref "M1") (pin "78") (pinfunction "78_78") (pintype "passive"))
    )
    (net (code "227") (name "/MGT111_TX3_N") (class "Default")
      (node (ref "M1") (pin "82") (pinfunction "82_82") (pintype "passive"))
    )
    (net (code "228") (name "/MGT111_TX3_P") (class "Default")
      (node (ref "M1") (pin "84") (pinfunction "84_84") (pintype "passive"))
    )
    (net (code "229") (name "/MGT112_REFCLK1_N") (class "Default")
      (node (ref "M1") (pin "119") (pinfunction "119_119") (pintype "passive"))
    )
    (net (code "230") (name "/MGT112_REFCLK1_P") (class "Default")
      (node (ref "M1") (pin "117") (pinfunction "117_117") (pintype "passive"))
    )
    (net (code "231") (name "/MGT112_RX0_N") (class "Default")
      (node (ref "M1") (pin "95") (pinfunction "95_95") (pintype "passive"))
    )
    (net (code "232") (name "/MGT112_RX0_P") (class "Default")
      (node (ref "M1") (pin "93") (pinfunction "93_93") (pintype "passive"))
    )
    (net (code "233") (name "/MGT112_RX1_N") (class "Default")
      (node (ref "M1") (pin "101") (pinfunction "101_101") (pintype "passive"))
    )
    (net (code "234") (name "/MGT112_RX1_P") (class "Default")
      (node (ref "M1") (pin "99") (pinfunction "99_99") (pintype "passive"))
    )
    (net (code "235") (name "/MGT112_RX2_N") (class "Default")
      (node (ref "M1") (pin "107") (pinfunction "107_107") (pintype "passive"))
    )
    (net (code "236") (name "/MGT112_RX2_P") (class "Default")
      (node (ref "M1") (pin "105") (pinfunction "105_105") (pintype "passive"))
    )
    (net (code "237") (name "/MGT112_RX3_N") (class "Default")
      (node (ref "M1") (pin "113") (pinfunction "113_113") (pintype "passive"))
    )
    (net (code "238") (name "/MGT112_RX3_P") (class "Default")
      (node (ref "M1") (pin "111") (pinfunction "111_111") (pintype "passive"))
    )
    (net (code "239") (name "/MGT112_TX0_N") (class "Default")
      (node (ref "M1") (pin "96") (pinfunction "96_96") (pintype "passive"))
    )
    (net (code "240") (name "/MGT112_TX0_P") (class "Default")
      (node (ref "M1") (pin "94") (pinfunction "94_94") (pintype "passive"))
    )
    (net (code "241") (name "/MGT112_TX1_N") (class "Default")
      (node (ref "M1") (pin "102") (pinfunction "102_102") (pintype "passive"))
    )
    (net (code "242") (name "/MGT112_TX1_P") (class "Default")
      (node (ref "M1") (pin "100") (pinfunction "100_100") (pintype "passive"))
    )
    (net (code "243") (name "/MGT112_TX2_N") (class "Default")
      (node (ref "M1") (pin "108") (pinfunction "108_108") (pintype "passive"))
    )
    (net (code "244") (name "/MGT112_TX2_P") (class "Default")
      (node (ref "M1") (pin "106") (pinfunction "106_106") (pintype "passive"))
    )
    (net (code "245") (name "/MGT112_TX3_N") (class "Default")
      (node (ref "M1") (pin "114") (pinfunction "114_114") (pintype "passive"))
    )
    (net (code "246") (name "/MGT112_TX3_P") (class "Default")
      (node (ref "M1") (pin "112") (pinfunction "112_112") (pintype "passive"))
    )
    (net (code "247") (name "1.0V") (class "Default")
      (node (ref "M1") (pin "121") (pinfunction "121_121") (pintype "passive"))
      (node (ref "M1") (pin "123") (pinfunction "123_123") (pintype "passive"))
      (node (ref "M1") (pin "125") (pinfunction "125_125") (pintype "passive"))
      (node (ref "M1") (pin "127") (pinfunction "127_127") (pintype "passive"))
      (node (ref "M1") (pin "129") (pinfunction "129_129") (pintype "passive"))
      (node (ref "M1") (pin "131") (pinfunction "131_131") (pintype "passive"))
      (node (ref "M1") (pin "133") (pinfunction "133_133") (pintype "passive"))
      (node (ref "M1") (pin "135") (pinfunction "135_135") (pintype "passive"))
      (node (ref "M1") (pin "137") (pinfunction "137_137") (pintype "passive"))
      (node (ref "M1") (pin "139") (pinfunction "139_139") (pintype "passive"))
      (node (ref "M1") (pin "141") (pinfunction "141_141") (pintype "passive"))
      (node (ref "M1") (pin "143") (pinfunction "143_143") (pintype "passive"))
      (node (ref "M1") (pin "145") (pinfunction "145_145") (pintype "passive"))
      (node (ref "M1") (pin "147") (pinfunction "147_147") (pintype "passive"))
    )
    (net (code "248") (name "1.0V_MGT") (class "Default")
      (node (ref "M1") (pin "122") (pinfunction "122_122") (pintype "passive"))
      (node (ref "M1") (pin "124") (pinfunction "124_124") (pintype "passive"))
      (node (ref "M1") (pin "126") (pinfunction "126_126") (pintype "passive"))
      (node (ref "M1") (pin "128") (pinfunction "128_128") (pintype "passive"))
      (node (ref "M1") (pin "130") (pinfunction "130_130") (pintype "passive"))
      (node (ref "M1") (pin "132") (pinfunction "132_132") (pintype "passive"))
      (node (ref "M1") (pin "134") (pinfunction "134_134") (pintype "passive"))
      (node (ref "M1") (pin "136") (pinfunction "136_136") (pintype "passive"))
    )
    (net (code "249") (name "1.2V_MGT") (class "Default")
      (node (ref "M1") (pin "138") (pinfunction "138_138") (pintype "passive"))
      (node (ref "M1") (pin "140") (pinfunction "140_140") (pintype "passive"))
      (node (ref "M1") (pin "142") (pinfunction "142_142") (pintype "passive"))
      (node (ref "M1") (pin "144") (pinfunction "144_144") (pintype "passive"))
      (node (ref "M1") (pin "146") (pinfunction "146_146") (pintype "passive"))
      (node (ref "M1") (pin "148") (pinfunction "148_148") (pintype "passive"))
    )
    (net (code "250") (name "1.5V_1.35V") (class "Default")
      (node (ref "M1") (pin "149") (pinfunction "149_149") (pintype "passive"))
      (node (ref "M1") (pin "151") (pinfunction "151_151") (pintype "passive"))
      (node (ref "M1") (pin "153") (pinfunction "153_153") (pintype "passive"))
      (node (ref "M1") (pin "155") (pinfunction "155_155") (pintype "passive"))
      (node (ref "M1") (pin "157") (pinfunction "157_157") (pintype "passive"))
      (node (ref "M1") (pin "159") (pinfunction "159_159") (pintype "passive"))
    )
    (net (code "251") (name "1.8V") (class "Default")
      (node (ref "M1") (pin "150") (pinfunction "150_150") (pintype "passive"))
      (node (ref "M1") (pin "152") (pinfunction "152_152") (pintype "passive"))
      (node (ref "M1") (pin "154") (pinfunction "154_154") (pintype "passive"))
      (node (ref "M1") (pin "156") (pinfunction "156_156") (pintype "passive"))
      (node (ref "M1") (pin "158") (pinfunction "158_158") (pintype "passive"))
      (node (ref "M1") (pin "160") (pinfunction "160_160") (pintype "passive"))
    )
    (net (code "252") (name "2.0V") (class "Default")
      (node (ref "M1") (pin "161") (pinfunction "161_161") (pintype "passive"))
      (node (ref "M1") (pin "163") (pinfunction "163_163") (pintype "passive"))
      (node (ref "M1") (pin "165") (pinfunction "165_165") (pintype "passive"))
      (node (ref "M1") (pin "167") (pinfunction "167_167") (pintype "passive"))
      (node (ref "M1") (pin "169") (pinfunction "169_169") (pintype "passive"))
    )
    (net (code "253") (name "2.5V") (class "Default")
      (node (ref "M1") (pin "162") (pinfunction "162_162") (pintype "passive"))
      (node (ref "M1") (pin "164") (pinfunction "164_164") (pintype "passive"))
      (node (ref "M1") (pin "166") (pinfunction "166_166") (pintype "passive"))
      (node (ref "M1") (pin "168") (pinfunction "168_168") (pintype "passive"))
      (node (ref "M1") (pin "170") (pinfunction "170_170") (pintype "passive"))
    )
    (net (code "254") (name "3.3V") (class "Default")
      (node (ref "M1") (pin "172") (pinfunction "172_172") (pintype "passive"))
      (node (ref "M1") (pin "174") (pinfunction "174_174") (pintype "passive"))
      (node (ref "M1") (pin "176") (pinfunction "176_176") (pintype "passive"))
      (node (ref "M1") (pin "178") (pinfunction "178_178") (pintype "passive"))
      (node (ref "M1") (pin "180") (pinfunction "180_180") (pintype "passive"))
    )
    (net (code "255") (name "AES_BATT") (class "Default")
      (node (ref "M1") (pin "B114") (pinfunction "114_B114") (pintype "passive"))
    )
    (net (code "256") (name "GND") (class "Default")
      (node (ref "M1") (pin "1") (pinfunction "1_1") (pintype "passive"))
      (node (ref "M1") (pin "103") (pinfunction "103_103") (pintype "passive"))
      (node (ref "M1") (pin "104") (pinfunction "104_104") (pintype "passive"))
      (node (ref "M1") (pin "109") (pinfunction "109_109") (pintype "passive"))
      (node (ref "M1") (pin "110") (pinfunction "110_110") (pintype "passive"))
      (node (ref "M1") (pin "115") (pinfunction "115_115") (pintype "passive"))
      (node (ref "M1") (pin "116") (pinfunction "116_116") (pintype "passive"))
      (node (ref "M1") (pin "13") (pinfunction "13_13") (pintype "passive"))
      (node (ref "M1") (pin "14") (pinfunction "14_14") (pintype "passive"))
      (node (ref "M1") (pin "19") (pinfunction "19_19") (pintype "passive"))
      (node (ref "M1") (pin "2") (pinfunction "2_2") (pintype "passive"))
      (node (ref "M1") (pin "20") (pinfunction "20_20") (pintype "passive"))
      (node (ref "M1") (pin "25") (pinfunction "25_25") (pintype "passive"))
      (node (ref "M1") (pin "26") (pinfunction "26_26") (pintype "passive"))
      (node (ref "M1") (pin "31") (pinfunction "31_31") (pintype "passive"))
      (node (ref "M1") (pin "32") (pinfunction "32_32") (pintype "passive"))
      (node (ref "M1") (pin "37") (pinfunction "37_37") (pintype "passive"))
      (node (ref "M1") (pin "38") (pinfunction "38_38") (pintype "passive"))
      (node (ref "M1") (pin "43") (pinfunction "43_43") (pintype "passive"))
      (node (ref "M1") (pin "44") (pinfunction "44_44") (pintype "passive"))
      (node (ref "M1") (pin "49") (pinfunction "49_49") (pintype "passive"))
      (node (ref "M1") (pin "50") (pinfunction "50_50") (pintype "passive"))
      (node (ref "M1") (pin "55") (pinfunction "55_55") (pintype "passive"))
      (node (ref "M1") (pin "56") (pinfunction "56_56") (pintype "passive"))
      (node (ref "M1") (pin "61") (pinfunction "61_61") (pintype "passive"))
      (node (ref "M1") (pin "62") (pinfunction "62_62") (pintype "passive"))
      (node (ref "M1") (pin "67") (pinfunction "67_67") (pintype "passive"))
      (node (ref "M1") (pin "68") (pinfunction "68_68") (pintype "passive"))
      (node (ref "M1") (pin "7") (pinfunction "7_7") (pintype "passive"))
      (node (ref "M1") (pin "73") (pinfunction "73_73") (pintype "passive"))
      (node (ref "M1") (pin "74") (pinfunction "74_74") (pintype "passive"))
      (node (ref "M1") (pin "79") (pinfunction "79_79") (pintype "passive"))
      (node (ref "M1") (pin "8") (pinfunction "8_8") (pintype "passive"))
      (node (ref "M1") (pin "80") (pinfunction "80_80") (pintype "passive"))
      (node (ref "M1") (pin "85") (pinfunction "85_85") (pintype "passive"))
      (node (ref "M1") (pin "86") (pinfunction "86_86") (pintype "passive"))
      (node (ref "M1") (pin "91") (pinfunction "91_91") (pintype "passive"))
      (node (ref "M1") (pin "92") (pinfunction "92_92") (pintype "passive"))
      (node (ref "M1") (pin "97") (pinfunction "97_97") (pintype "passive"))
      (node (ref "M1") (pin "98") (pinfunction "98_98") (pintype "passive"))
      (node (ref "M1") (pin "B1") (pinfunction "GND_B1") (pintype "passive"))
      (node (ref "M1") (pin "B101") (pinfunction "GND_B101") (pintype "passive"))
      (node (ref "M1") (pin "B102") (pinfunction "GND_B102") (pintype "passive"))
      (node (ref "M1") (pin "B103") (pinfunction "103_B103") (pintype "passive"))
      (node (ref "M1") (pin "B104") (pinfunction "104_B104") (pintype "passive"))
      (node (ref "M1") (pin "B105") (pinfunction "105_B105") (pintype "passive"))
      (node (ref "M1") (pin "B106") (pinfunction "106_B106") (pintype "passive"))
      (node (ref "M1") (pin "B107") (pinfunction "107_B107") (pintype "passive"))
      (node (ref "M1") (pin "B108") (pinfunction "108_B108") (pintype "passive"))
      (node (ref "M1") (pin "B109") (pinfunction "109_B109") (pintype "passive"))
      (node (ref "M1") (pin "B110") (pinfunction "110_B110") (pintype "passive"))
      (node (ref "M1") (pin "B111") (pinfunction "111_B111") (pintype "passive"))
      (node (ref "M1") (pin "B112") (pinfunction "112_B112") (pintype "passive"))
      (node (ref "M1") (pin "B113") (pinfunction "113_B113") (pintype "passive"))
      (node (ref "M1") (pin "B119") (pinfunction "GND_B119") (pintype "passive"))
      (node (ref "M1") (pin "B120") (pinfunction "GND_B120") (pintype "passive"))
      (node (ref "M1") (pin "B129") (pinfunction "129_B129") (pintype "passive"))
      (node (ref "M1") (pin "B130") (pinfunction "130_B130") (pintype "passive"))
      (node (ref "M1") (pin "B139") (pinfunction "GND_B139") (pintype "passive"))
      (node (ref "M1") (pin "B140") (pinfunction "GND_B140") (pintype "passive"))
      (node (ref "M1") (pin "B159") (pinfunction "GND_B159") (pintype "passive"))
      (node (ref "M1") (pin "B160") (pinfunction "GND_B160") (pintype "passive"))
      (node (ref "M1") (pin "B169") (pinfunction "169_B169") (pintype "passive"))
      (node (ref "M1") (pin "B170") (pinfunction "170_B170") (pintype "passive"))
      (node (ref "M1") (pin "B179") (pinfunction "GND_B179") (pintype "passive"))
      (node (ref "M1") (pin "B180") (pinfunction "GND_B180") (pintype "passive"))
      (node (ref "M1") (pin "B189") (pinfunction "189_B189") (pintype "passive"))
      (node (ref "M1") (pin "B190") (pinfunction "190_B190") (pintype "passive"))
      (node (ref "M1") (pin "B199") (pinfunction "GND_B199") (pintype "passive"))
      (node (ref "M1") (pin "B2") (pinfunction "GND_B2") (pintype "passive"))
      (node (ref "M1") (pin "B200") (pinfunction "GND_B200") (pintype "passive"))
      (node (ref "M1") (pin "B209") (pinfunction "209_B209") (pintype "passive"))
      (node (ref "M1") (pin "B21") (pinfunction "GND_B21") (pintype "passive"))
      (node (ref "M1") (pin "B210") (pinfunction "210_B210") (pintype "passive"))
      (node (ref "M1") (pin "B219") (pinfunction "GND_B219") (pintype "passive"))
      (node (ref "M1") (pin "B22") (pinfunction "GND_B22") (pintype "passive"))
      (node (ref "M1") (pin "B220") (pinfunction "GND_B220") (pintype "passive"))
      (node (ref "M1") (pin "B31") (pinfunction "31_B31") (pintype "passive"))
      (node (ref "M1") (pin "B32") (pinfunction "32_B32") (pintype "passive"))
      (node (ref "M1") (pin "B41") (pinfunction "GND_B41") (pintype "passive"))
      (node (ref "M1") (pin "B42") (pinfunction "GND_B42") (pintype "passive"))
      (node (ref "M1") (pin "B51") (pinfunction "51_B51") (pintype "passive"))
      (node (ref "M1") (pin "B52") (pinfunction "52_B52") (pintype "passive"))
      (node (ref "M1") (pin "B61") (pinfunction "GND_B61") (pintype "passive"))
      (node (ref "M1") (pin "B62") (pinfunction "GND_B62") (pintype "passive"))
      (node (ref "M1") (pin "B81") (pinfunction "GND_B81") (pintype "passive"))
      (node (ref "M1") (pin "B82") (pinfunction "GND_B82") (pintype "passive"))
      (node (ref "M1") (pin "B91") (pinfunction "91_B91") (pintype "passive"))
      (node (ref "M1") (pin "B92") (pinfunction "92_B92") (pintype "passive"))
      (node (ref "M1") (pin "BMP1") (pinfunction "MP1_BMP1") (pintype "passive"))
      (node (ref "M1") (pin "BMP2") (pinfunction "MP2_BMP2") (pintype "passive"))
      (node (ref "M1") (pin "M1") (pinfunction "M1_M1") (pintype "passive"))
      (node (ref "M1") (pin "M2") (pinfunction "M2_M2") (pintype "passive"))
      (node (ref "M1") (pin "s1") (pinfunction "s1_s1") (pintype "passive"))
      (node (ref "M1") (pin "s10") (pinfunction "s10_s10") (pintype "passive"))
      (node (ref "M1") (pin "s11") (pinfunction "s11_s11") (pintype "passive"))
      (node (ref "M1") (pin "s12") (pinfunction "s12_s12") (pintype "passive"))
      (node (ref "M1") (pin "s2") (pinfunction "s2_s2") (pintype "passive"))
      (node (ref "M1") (pin "s3") (pinfunction "s3_s3") (pintype "passive"))
      (node (ref "M1") (pin "s4") (pinfunction "s4_s4") (pintype "passive"))
      (node (ref "M1") (pin "s5") (pinfunction "s5_s5") (pintype "passive"))
      (node (ref "M1") (pin "s6") (pinfunction "s6_s6") (pintype "passive"))
      (node (ref "M1") (pin "s7") (pinfunction "s7_s7") (pintype "passive"))
      (node (ref "M1") (pin "s8") (pinfunction "s8_s8") (pintype "passive"))
      (node (ref "M1") (pin "s9") (pinfunction "s9_s9") (pintype "passive"))
    )
    (net (code "257") (name "VADJ") (class "Default")
      (node (ref "M1") (pin "171") (pinfunction "171_171") (pintype "passive"))
      (node (ref "M1") (pin "173") (pinfunction "173_173") (pintype "passive"))
      (node (ref "M1") (pin "175") (pinfunction "175_175") (pintype "passive"))
      (node (ref "M1") (pin "177") (pinfunction "177_177") (pintype "passive"))
      (node (ref "M1") (pin "179") (pinfunction "179_179") (pintype "passive"))
    )
    (net (code "258") (name "unconnected-(M1-Pad57)") (class "Default")
      (node (ref "M1") (pin "57") (pinfunction "57_57") (pintype "passive"))
    )
    (net (code "259") (name "unconnected-(M1-Pad59)") (class "Default")
      (node (ref "M1") (pin "59") (pinfunction "59_59") (pintype "passive"))
    )
    (net (code "260") (name "unconnected-(M1-Pad118)") (class "Default")
      (node (ref "M1") (pin "118") (pinfunction "118_118") (pintype "passive"))
    )
    (net (code "261") (name "unconnected-(M1-Pad120)") (class "Default")
      (node (ref "M1") (pin "120") (pinfunction "120_120") (pintype "passive"))
    )
    (net (code "262") (name "unconnected-(M1G-R1-PadBR1)") (class "Default")
      (node (ref "M1") (pin "BR1") (pinfunction "R1_BR1") (pintype "passive"))
    )
    (net (code "263") (name "unconnected-(M1G-R2-PadBR2)") (class "Default")
      (node (ref "M1") (pin "BR2") (pinfunction "R2_BR2") (pintype "passive"))
    )
  )
)
